# hw-demo03.net
KiCad netlist of a schematic drawn in EAGLE
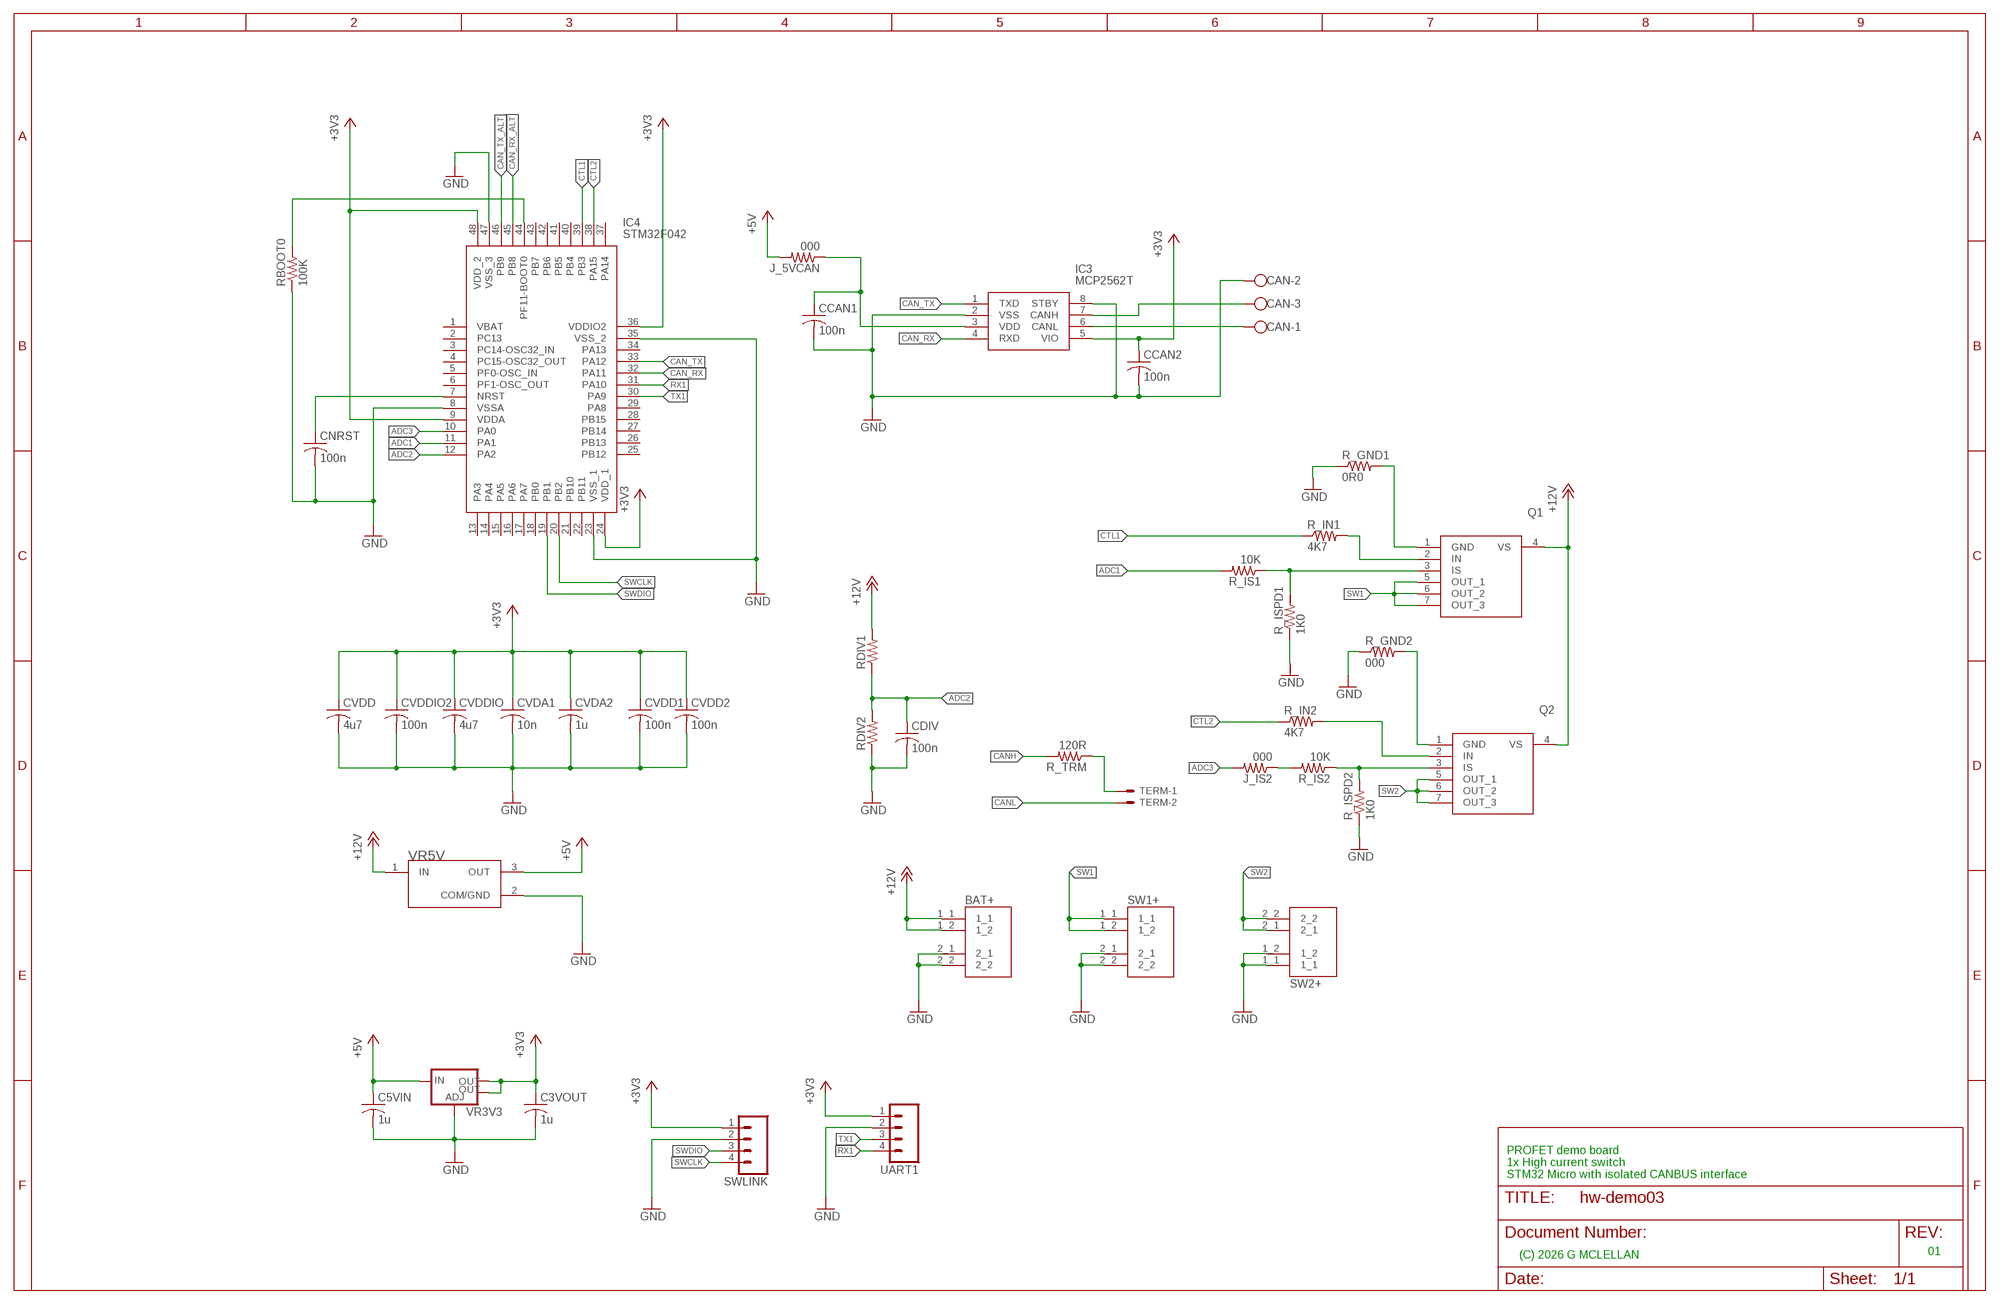
[diagram p0: schematic, sheet 1]

(export (version "E")
  (design (tool "Eeschema 10.0.6"))
  (components
    (comp (ref "BAT+")
      (value "VP0265840000G")
      (footprint "eagle-import:AMPHENOL_VP0265840000G")
      (fields (field (name "MANUFACTURER") "Amphenol Anytek"))
      (libsource (lib "eagle-import") (part "VP0265840000G"))
    )
    (comp (ref "C3VOUT")
      (value "1u")
      (footprint "eagle-import:C0805K")
      (libsource (lib "eagle-import") (part "C-USC0805K"))
    )
    (comp (ref "C5VIN")
      (value "1u")
      (footprint "eagle-import:C1206K")
      (libsource (lib "eagle-import") (part "C-USC1206K"))
    )
    (comp (ref "CAN")
      (value "W237-103")
      (footprint "eagle-import:W237-103")
      (fields (field (name "MPN") "237-103"))
      (libsource (lib "eagle-import") (part "W237-103"))
    )
    (comp (ref "CCAN1")
      (value "100n")
      (footprint "eagle-import:C0603K")
      (libsource (lib "eagle-import") (part "C-USC0603K"))
    )
    (comp (ref "CCAN2")
      (value "100n")
      (footprint "eagle-import:C0603K")
      (libsource (lib "eagle-import") (part "C-USC0603K"))
    )
    (comp (ref "CDIV")
      (value "100n")
      (footprint "eagle-import:C0603K")
      (libsource (lib "eagle-import") (part "C-USC0603K"))
    )
    (comp (ref "CNRST")
      (value "100n")
      (footprint "eagle-import:C0603K")
      (libsource (lib "eagle-import") (part "C-USC0603K"))
    )
    (comp (ref "CVDA1")
      (value "10n")
      (footprint "eagle-import:C0603K")
      (libsource (lib "eagle-import") (part "C-USC0603K"))
    )
    (comp (ref "CVDA2")
      (value "1u")
      (footprint "eagle-import:C0603K")
      (libsource (lib "eagle-import") (part "C-USC0603K"))
    )
    (comp (ref "CVDD")
      (value "4u7")
      (footprint "eagle-import:C0603K")
      (libsource (lib "eagle-import") (part "C-USC0603K"))
    )
    (comp (ref "CVDD1")
      (value "100n")
      (footprint "eagle-import:C0603K")
      (libsource (lib "eagle-import") (part "C-USC0603K"))
    )
    (comp (ref "CVDD2")
      (value "100n")
      (footprint "eagle-import:C0603K")
      (libsource (lib "eagle-import") (part "C-USC0603K"))
    )
    (comp (ref "CVDDIO")
      (value "4u7")
      (footprint "eagle-import:C0603K")
      (libsource (lib "eagle-import") (part "C-USC0603K"))
    )
    (comp (ref "CVDDIO2")
      (value "100n")
      (footprint "eagle-import:C0603K")
      (libsource (lib "eagle-import") (part "C-USC0603K"))
    )
    (comp (ref "IC3")
      (value "MCP2562T")
      (footprint "eagle-import:SOIC127P600X175-8N")
      (fields
        (field (name "MANUFACTURER_PART_NUMBER") "MCP2562T-H/SN")
        (field (name "MOUSER_PART_NUMBER") "579-MCP2562T-H/SN")
      )
      (libsource (lib "eagle-import") (part "MCP2562T-H_SN"))
    )
    (comp (ref "IC4")
      (value "STM32F042")
      (footprint "eagle-import:QFP50P900X900X160-48N")
      (fields
        (field (name "MANUFACTURER_PART_NUMBER") "STM32F042C6T7")
        (field (name "MOUSER_PART_NUMBER") "511-STM32F042C6T7")
      )
      (libsource (lib "eagle-import") (part "STM32F042C6T7"))
    )
    (comp (ref "J_5VCAN")
      (value "000")
      (footprint "eagle-import:0207_15")
      (libsource (lib "eagle-import") (part "R-US_0207/15"))
    )
    (comp (ref "J_IS2")
      (value "000")
      (footprint "eagle-import:0207_15")
      (libsource (lib "eagle-import") (part "R-US_0207/15"))
    )
    (comp (ref "Q1")
      (value "BTS500101TADATMA2")
      (footprint "eagle-import:BTS500101TADATMA2")
      (fields (field (name "MOUSER_PART_NUMBER") "726-BTS500101TADATM2"))
      (libsource (lib "eagle-import") (part "BTS500101TADATMA2"))
    )
    (comp (ref "Q2")
      (value "BTS500101TADATMA2")
      (footprint "eagle-import:BTS500101TADATMA2")
      (fields (field (name "MOUSER_PART_NUMBER") "726-BTS500101TADATM2"))
      (libsource (lib "eagle-import") (part "BTS500101TADATMA2"))
    )
    (comp (ref "RBOOT0")
      (value "100K")
      (footprint "eagle-import:R0603")
      (libsource (lib "eagle-import") (part "R-US_R0603"))
    )
    (comp (ref "RDIV1")
      (value "R-US_R0805")
      (footprint "eagle-import:R0805")
      (libsource (lib "eagle-import") (part "R-US_R0805"))
    )
    (comp (ref "RDIV2")
      (value "R-US_R0805")
      (footprint "eagle-import:R0805")
      (libsource (lib "eagle-import") (part "R-US_R0805"))
    )
    (comp (ref "R_GND1")
      (value "0R0")
      (footprint "eagle-import:R1206W")
      (libsource (lib "eagle-import") (part "R-US_R1206W"))
    )
    (comp (ref "R_GND2")
      (value "000")
      (footprint "eagle-import:R1206W")
      (libsource (lib "eagle-import") (part "R-US_R1206W"))
    )
    (comp (ref "R_IN1")
      (value "4K7")
      (footprint "eagle-import:0207_10")
      (libsource (lib "eagle-import") (part "R-US_0207/10"))
    )
    (comp (ref "R_IN2")
      (value "4K7")
      (footprint "eagle-import:0204_7")
      (libsource (lib "eagle-import") (part "R-US_0204/7"))
    )
    (comp (ref "R_IS1")
      (value "10K")
      (footprint "eagle-import:0204_7")
      (libsource (lib "eagle-import") (part "R-US_0204/7"))
    )
    (comp (ref "R_IS2")
      (value "10K")
      (footprint "eagle-import:0204_7")
      (libsource (lib "eagle-import") (part "R-US_0204/7"))
    )
    (comp (ref "R_ISPD1")
      (value "1K0")
      (footprint "eagle-import:0204_7")
      (libsource (lib "eagle-import") (part "R-US_0204/7"))
    )
    (comp (ref "R_ISPD2")
      (value "1K0")
      (footprint "eagle-import:0204_7")
      (libsource (lib "eagle-import") (part "R-US_0204/7"))
    )
    (comp (ref "R_TRM")
      (value "120R")
      (footprint "eagle-import:0204_7")
      (libsource (lib "eagle-import") (part "R-US_0204/7"))
    )
    (comp (ref "SW1+")
      (value "VP0265840000G")
      (footprint "eagle-import:AMPHENOL_VP0265840000G")
      (fields (field (name "MANUFACTURER") "Amphenol Anytek"))
      (libsource (lib "eagle-import") (part "VP0265840000G"))
    )
    (comp (ref "SW2+")
      (value "VP0265840000G")
      (footprint "eagle-import:AMPHENOL_VP0265840000G")
      (fields (field (name "MANUFACTURER") "Amphenol Anytek"))
      (libsource (lib "eagle-import") (part "VP0265840000G"))
    )
    (comp (ref "SWLINK")
      (value "M04LOCK")
      (footprint "eagle-import:1X04_LOCK")
      (libsource (lib "eagle-import") (part "M04LOCK"))
    )
    (comp (ref "TERM")
      (value "22-23-2021")
      (footprint "eagle-import:22-23-2021")
      (fields (field (name "MF") "MOLEX"))
      (libsource (lib "eagle-import") (part "22-23-2021"))
    )
    (comp (ref "UART1")
      (value "M04LOCK")
      (footprint "eagle-import:1X04_LOCK")
      (libsource (lib "eagle-import") (part "M04LOCK"))
    )
    (comp (ref "VR3V3")
      (value "V_REG_LM1117SOT223")
      (footprint "eagle-import:SOT223")
      (libsource (lib "eagle-import") (part "V_REG_LM1117SOT223"))
    )
    (comp (ref "VR5V")
      (value "OKI-78SR-5/1.5-W36-C")
      (footprint "eagle-import:CONV_OKI-78SR-5_1.5-W36-C")
      (fields (field (name "MANUFACTURER") "Murata"))
      (libsource (lib "eagle-import") (part "OKI-78SR-5/1.5-W36-C"))
    )
  )
  (nets
    (net (code "1") (name "+3V3") (class "Default")
      (node (ref "C3VOUT") (pin "1") (pinfunction "1_1") (pintype "passive"))
      (node (ref "CCAN2") (pin "1") (pinfunction "1_1") (pintype "passive"))
      (node (ref "CVDA1") (pin "1") (pinfunction "1_1") (pintype "passive"))
      (node (ref "CVDA2") (pin "1") (pinfunction "1_1") (pintype "passive"))
      (node (ref "CVDD") (pin "1") (pinfunction "1_1") (pintype "passive"))
      (node (ref "CVDD1") (pin "1") (pinfunction "1_1") (pintype "passive"))
      (node (ref "CVDD2") (pin "1") (pinfunction "1_1") (pintype "passive"))
      (node (ref "CVDDIO") (pin "1") (pinfunction "1_1") (pintype "passive"))
      (node (ref "CVDDIO2") (pin "1") (pinfunction "1_1") (pintype "passive"))
      (node (ref "IC3") (pin "5") (pinfunction "VIO_5") (pintype "bidirectional"))
      (node (ref "IC4") (pin "24") (pinfunction "VDD_1_24") (pintype "bidirectional"))
      (node (ref "IC4") (pin "36") (pinfunction "VDDIO2_36") (pintype "bidirectional"))
      (node (ref "IC4") (pin "48") (pinfunction "VDD_2_48") (pintype "bidirectional"))
      (node (ref "IC4") (pin "9") (pinfunction "VDDA_9") (pintype "bidirectional"))
      (node (ref "SWLINK") (pin "1") (pinfunction "1_1") (pintype "passive"))
      (node (ref "UART1") (pin "1") (pinfunction "1_1") (pintype "passive"))
      (node (ref "VR3V3") (pin "2") (pinfunction "OUT_2") (pintype "output"))
      (node (ref "VR3V3") (pin "4") (pinfunction "OUT_4") (pintype "output"))
    )
    (net (code "2") (name "+5V") (class "Default")
      (node (ref "C5VIN") (pin "1") (pinfunction "1_1") (pintype "passive"))
      (node (ref "J_5VCAN") (pin "2") (pinfunction "2_2") (pintype "passive"))
      (node (ref "VR3V3") (pin "3") (pinfunction "IN_3") (pintype "input"))
      (node (ref "VR5V") (pin "3") (pinfunction "OUT_3") (pintype "output"))
    )
    (net (code "3") (name "+12V") (class "Default")
      (node (ref "BAT+") (pin "1_1") (pinfunction "1_1_1_1") (pintype "passive"))
      (node (ref "BAT+") (pin "1_2") (pinfunction "1_2_1_2") (pintype "passive"))
      (node (ref "Q1") (pin "4") (pinfunction "VS_4") (pintype "bidirectional"))
      (node (ref "Q2") (pin "4") (pinfunction "VS_4") (pintype "bidirectional"))
      (node (ref "RDIV1") (pin "2") (pinfunction "2_2") (pintype "passive"))
      (node (ref "VR5V") (pin "1") (pinfunction "IN_1") (pintype "input"))
    )
    (net (code "4") (name "ADC1") (class "Default")
      (node (ref "IC4") (pin "11") (pinfunction "PA1_11") (pintype "bidirectional"))
      (node (ref "R_IS1") (pin "2") (pinfunction "2_2") (pintype "passive"))
    )
    (net (code "5") (name "ADC2") (class "Default")
      (node (ref "CDIV") (pin "1") (pinfunction "1_1") (pintype "passive"))
      (node (ref "IC4") (pin "12") (pinfunction "PA2_12") (pintype "bidirectional"))
      (node (ref "RDIV1") (pin "1") (pinfunction "1_1") (pintype "passive"))
      (node (ref "RDIV2") (pin "2") (pinfunction "2_2") (pintype "passive"))
    )
    (net (code "6") (name "ADC3") (class "Default")
      (node (ref "IC4") (pin "10") (pinfunction "PA0_10") (pintype "bidirectional"))
      (node (ref "J_IS2") (pin "2") (pinfunction "2_2") (pintype "passive"))
    )
    (net (code "7") (name "CANH") (class "Default")
      (node (ref "CAN") (pin "3") (pinfunction "KL_3") (pintype "passive"))
      (node (ref "IC3") (pin "7") (pinfunction "CANH_7") (pintype "bidirectional"))
      (node (ref "R_TRM") (pin "2") (pinfunction "2_2") (pintype "passive"))
    )
    (net (code "8") (name "CANL") (class "Default")
      (node (ref "CAN") (pin "1") (pinfunction "KL_1") (pintype "passive"))
      (node (ref "IC3") (pin "6") (pinfunction "CANL_6") (pintype "bidirectional"))
      (node (ref "TERM") (pin "2") (pinfunction "S_2") (pintype "passive"))
    )
    (net (code "9") (name "CAN_RX") (class "Default")
      (node (ref "IC3") (pin "4") (pinfunction "RXD_4") (pintype "bidirectional"))
      (node (ref "IC4") (pin "32") (pinfunction "PA11_32") (pintype "bidirectional"))
    )
    (net (code "10") (name "CAN_RX_ALT") (class "Default")
      (node (ref "IC4") (pin "45") (pinfunction "PB8_45") (pintype "bidirectional"))
    )
    (net (code "11") (name "CAN_TX") (class "Default")
      (node (ref "IC3") (pin "1") (pinfunction "TXD_1") (pintype "bidirectional"))
      (node (ref "IC4") (pin "33") (pinfunction "PA12_33") (pintype "bidirectional"))
    )
    (net (code "12") (name "CAN_TX_ALT") (class "Default")
      (node (ref "IC4") (pin "46") (pinfunction "PB9_46") (pintype "bidirectional"))
    )
    (net (code "13") (name "CTL1") (class "Default")
      (node (ref "IC4") (pin "39") (pinfunction "PB3_39") (pintype "bidirectional"))
      (node (ref "R_IN1") (pin "1") (pinfunction "1_1") (pintype "passive"))
    )
    (net (code "14") (name "CTL2") (class "Default")
      (node (ref "IC4") (pin "38") (pinfunction "PA15_38") (pintype "bidirectional"))
      (node (ref "R_IN2") (pin "1") (pinfunction "1_1") (pintype "passive"))
    )
    (net (code "15") (name "GND") (class "Default")
      (node (ref "BAT+") (pin "2_1") (pinfunction "2_1_2_1") (pintype "passive"))
      (node (ref "BAT+") (pin "2_2") (pinfunction "2_2_2_2") (pintype "passive"))
      (node (ref "C3VOUT") (pin "2") (pinfunction "2_2") (pintype "passive"))
      (node (ref "C5VIN") (pin "2") (pinfunction "2_2") (pintype "passive"))
      (node (ref "CAN") (pin "2") (pinfunction "KL_2") (pintype "passive"))
      (node (ref "CCAN1") (pin "2") (pinfunction "2_2") (pintype "passive"))
      (node (ref "CCAN2") (pin "2") (pinfunction "2_2") (pintype "passive"))
      (node (ref "CDIV") (pin "2") (pinfunction "2_2") (pintype "passive"))
      (node (ref "CNRST") (pin "2") (pinfunction "2_2") (pintype "passive"))
      (node (ref "CVDA1") (pin "2") (pinfunction "2_2") (pintype "passive"))
      (node (ref "CVDA2") (pin "2") (pinfunction "2_2") (pintype "passive"))
      (node (ref "CVDD") (pin "2") (pinfunction "2_2") (pintype "passive"))
      (node (ref "CVDD1") (pin "2") (pinfunction "2_2") (pintype "passive"))
      (node (ref "CVDD2") (pin "2") (pinfunction "2_2") (pintype "passive"))
      (node (ref "CVDDIO") (pin "2") (pinfunction "2_2") (pintype "passive"))
      (node (ref "CVDDIO2") (pin "2") (pinfunction "2_2") (pintype "passive"))
      (node (ref "IC3") (pin "2") (pinfunction "VSS_2") (pintype "bidirectional"))
      (node (ref "IC3") (pin "8") (pinfunction "STBY_8") (pintype "bidirectional"))
      (node (ref "IC4") (pin "23") (pinfunction "VSS_1_23") (pintype "bidirectional"))
      (node (ref "IC4") (pin "35") (pinfunction "VSS_2_35") (pintype "bidirectional"))
      (node (ref "IC4") (pin "47") (pinfunction "VSS_3_47") (pintype "bidirectional"))
      (node (ref "IC4") (pin "8") (pinfunction "VSSA_8") (pintype "bidirectional"))
      (node (ref "RBOOT0") (pin "1") (pinfunction "1_1") (pintype "passive"))
      (node (ref "RDIV2") (pin "1") (pinfunction "1_1") (pintype "passive"))
      (node (ref "R_GND1") (pin "1") (pinfunction "1_1") (pintype "passive"))
      (node (ref "R_GND2") (pin "1") (pinfunction "1_1") (pintype "passive"))
      (node (ref "R_ISPD1") (pin "1") (pinfunction "1_1") (pintype "passive"))
      (node (ref "R_ISPD2") (pin "1") (pinfunction "1_1") (pintype "passive"))
      (node (ref "SW1+") (pin "2_1") (pinfunction "2_1_2_1") (pintype "passive"))
      (node (ref "SW1+") (pin "2_2") (pinfunction "2_2_2_2") (pintype "passive"))
      (node (ref "SW2+") (pin "1_1") (pinfunction "1_1_1_1") (pintype "passive"))
      (node (ref "SW2+") (pin "1_2") (pinfunction "1_2_1_2") (pintype "passive"))
      (node (ref "SWLINK") (pin "2") (pinfunction "2_2") (pintype "passive"))
      (node (ref "UART1") (pin "2") (pinfunction "2_2") (pintype "passive"))
      (node (ref "VR3V3") (pin "1") (pinfunction "ADJ_1") (pintype "input"))
      (node (ref "VR5V") (pin "2") (pinfunction "COM/GND_2") (pintype "power_in"))
    )
    (net (code "16") (name "Net-(IC3-VDD)") (class "Default")
      (node (ref "CCAN1") (pin "1") (pinfunction "1_1") (pintype "passive"))
      (node (ref "IC3") (pin "3") (pinfunction "VDD_3") (pintype "bidirectional"))
      (node (ref "J_5VCAN") (pin "1") (pinfunction "1_1") (pintype "passive"))
    )
    (net (code "17") (name "Net-(IC4-NRST)") (class "Default")
      (node (ref "CNRST") (pin "1") (pinfunction "1_1") (pintype "passive"))
      (node (ref "IC4") (pin "7") (pinfunction "NRST_7") (pintype "bidirectional"))
    )
    (net (code "18") (name "Net-(IC4-PF11-BOOT0)") (class "Default")
      (node (ref "IC4") (pin "44") (pinfunction "PF11-BOOT0_44") (pintype "bidirectional"))
      (node (ref "RBOOT0") (pin "2") (pinfunction "2_2") (pintype "passive"))
    )
    (net (code "19") (name "Net-(J_IS2-Pad1)") (class "Default")
      (node (ref "J_IS2") (pin "1") (pinfunction "1_1") (pintype "passive"))
      (node (ref "R_IS2") (pin "2") (pinfunction "2_2") (pintype "passive"))
    )
    (net (code "20") (name "Net-(Q1-GND)") (class "Default")
      (node (ref "Q1") (pin "1") (pinfunction "GND_1") (pintype "bidirectional"))
      (node (ref "R_GND1") (pin "2") (pinfunction "2_2") (pintype "passive"))
    )
    (net (code "21") (name "Net-(Q1-IN)") (class "Default")
      (node (ref "Q1") (pin "2") (pinfunction "IN_2") (pintype "bidirectional"))
      (node (ref "R_IN1") (pin "2") (pinfunction "2_2") (pintype "passive"))
    )
    (net (code "22") (name "Net-(Q1-IS)") (class "Default")
      (node (ref "Q1") (pin "3") (pinfunction "IS_3") (pintype "bidirectional"))
      (node (ref "R_IS1") (pin "1") (pinfunction "1_1") (pintype "passive"))
      (node (ref "R_ISPD1") (pin "2") (pinfunction "2_2") (pintype "passive"))
    )
    (net (code "23") (name "Net-(Q2-GND)") (class "Default")
      (node (ref "Q2") (pin "1") (pinfunction "GND_1") (pintype "bidirectional"))
      (node (ref "R_GND2") (pin "2") (pinfunction "2_2") (pintype "passive"))
    )
    (net (code "24") (name "Net-(Q2-IN)") (class "Default")
      (node (ref "Q2") (pin "2") (pinfunction "IN_2") (pintype "bidirectional"))
      (node (ref "R_IN2") (pin "2") (pinfunction "2_2") (pintype "passive"))
    )
    (net (code "25") (name "Net-(Q2-IS)") (class "Default")
      (node (ref "Q2") (pin "3") (pinfunction "IS_3") (pintype "bidirectional"))
      (node (ref "R_IS2") (pin "1") (pinfunction "1_1") (pintype "passive"))
      (node (ref "R_ISPD2") (pin "2") (pinfunction "2_2") (pintype "passive"))
    )
    (net (code "26") (name "Net-(TERMA-S)") (class "Default")
      (node (ref "R_TRM") (pin "1") (pinfunction "1_1") (pintype "passive"))
      (node (ref "TERM") (pin "1") (pinfunction "S_1") (pintype "passive"))
    )
    (net (code "27") (name "RX1") (class "Default")
      (node (ref "IC4") (pin "31") (pinfunction "PA10_31") (pintype "bidirectional"))
      (node (ref "UART1") (pin "4") (pinfunction "4_4") (pintype "passive"))
    )
    (net (code "28") (name "SW1") (class "Default")
      (node (ref "Q1") (pin "5") (pinfunction "OUT_1_5") (pintype "bidirectional"))
      (node (ref "Q1") (pin "6") (pinfunction "OUT_2_6") (pintype "bidirectional"))
      (node (ref "Q1") (pin "7") (pinfunction "OUT_3_7") (pintype "bidirectional"))
      (node (ref "SW1+") (pin "1_1") (pinfunction "1_1_1_1") (pintype "passive"))
      (node (ref "SW1+") (pin "1_2") (pinfunction "1_2_1_2") (pintype "passive"))
    )
    (net (code "29") (name "SW2") (class "Default")
      (node (ref "Q2") (pin "5") (pinfunction "OUT_1_5") (pintype "bidirectional"))
      (node (ref "Q2") (pin "6") (pinfunction "OUT_2_6") (pintype "bidirectional"))
      (node (ref "Q2") (pin "7") (pinfunction "OUT_3_7") (pintype "bidirectional"))
      (node (ref "SW2+") (pin "2_1") (pinfunction "2_1_2_1") (pintype "passive"))
      (node (ref "SW2+") (pin "2_2") (pinfunction "2_2_2_2") (pintype "passive"))
    )
    (net (code "30") (name "SWCLK") (class "Default")
      (node (ref "IC4") (pin "20") (pinfunction "PB2_20") (pintype "bidirectional"))
      (node (ref "SWLINK") (pin "4") (pinfunction "4_4") (pintype "passive"))
    )
    (net (code "31") (name "SWDIO") (class "Default")
      (node (ref "IC4") (pin "19") (pinfunction "PB1_19") (pintype "bidirectional"))
      (node (ref "SWLINK") (pin "3") (pinfunction "3_3") (pintype "passive"))
    )
    (net (code "32") (name "TX1") (class "Default")
      (node (ref "IC4") (pin "30") (pinfunction "PA9_30") (pintype "bidirectional"))
      (node (ref "UART1") (pin "3") (pinfunction "3_3") (pintype "passive"))
    )
    (net (code "33") (name "unconnected-(IC4-PA3-Pad13)") (class "Default")
      (node (ref "IC4") (pin "13") (pinfunction "PA3_13") (pintype "bidirectional"))
    )
    (net (code "34") (name "unconnected-(IC4-PA4-Pad14)") (class "Default")
      (node (ref "IC4") (pin "14") (pinfunction "PA4_14") (pintype "bidirectional"))
    )
    (net (code "35") (name "unconnected-(IC4-PA5-Pad15)") (class "Default")
      (node (ref "IC4") (pin "15") (pinfunction "PA5_15") (pintype "bidirectional"))
    )
    (net (code "36") (name "unconnected-(IC4-PA6-Pad16)") (class "Default")
      (node (ref "IC4") (pin "16") (pinfunction "PA6_16") (pintype "bidirectional"))
    )
    (net (code "37") (name "unconnected-(IC4-PA7-Pad17)") (class "Default")
      (node (ref "IC4") (pin "17") (pinfunction "PA7_17") (pintype "bidirectional"))
    )
    (net (code "38") (name "unconnected-(IC4-PA8-Pad29)") (class "Default")
      (node (ref "IC4") (pin "29") (pinfunction "PA8_29") (pintype "bidirectional"))
    )
    (net (code "39") (name "unconnected-(IC4-PA13-Pad34)") (class "Default")
      (node (ref "IC4") (pin "34") (pinfunction "PA13_34") (pintype "bidirectional"))
    )
    (net (code "40") (name "unconnected-(IC4-PA14-Pad37)") (class "Default")
      (node (ref "IC4") (pin "37") (pinfunction "PA14_37") (pintype "bidirectional"))
    )
    (net (code "41") (name "unconnected-(IC4-PB0-Pad18)") (class "Default")
      (node (ref "IC4") (pin "18") (pinfunction "PB0_18") (pintype "bidirectional"))
    )
    (net (code "42") (name "unconnected-(IC4-PB4-Pad40)") (class "Default")
      (node (ref "IC4") (pin "40") (pinfunction "PB4_40") (pintype "bidirectional"))
    )
    (net (code "43") (name "unconnected-(IC4-PB5-Pad41)") (class "Default")
      (node (ref "IC4") (pin "41") (pinfunction "PB5_41") (pintype "bidirectional"))
    )
    (net (code "44") (name "unconnected-(IC4-PB6-Pad42)") (class "Default")
      (node (ref "IC4") (pin "42") (pinfunction "PB6_42") (pintype "bidirectional"))
    )
    (net (code "45") (name "unconnected-(IC4-PB7-Pad43)") (class "Default")
      (node (ref "IC4") (pin "43") (pinfunction "PB7_43") (pintype "bidirectional"))
    )
    (net (code "46") (name "unconnected-(IC4-PB10-Pad21)") (class "Default")
      (node (ref "IC4") (pin "21") (pinfunction "PB10_21") (pintype "bidirectional"))
    )
    (net (code "47") (name "unconnected-(IC4-PB11-Pad22)") (class "Default")
      (node (ref "IC4") (pin "22") (pinfunction "PB11_22") (pintype "bidirectional"))
    )
    (net (code "48") (name "unconnected-(IC4-PB12-Pad25)") (class "Default")
      (node (ref "IC4") (pin "25") (pinfunction "PB12_25") (pintype "bidirectional"))
    )
    (net (code "49") (name "unconnected-(IC4-PB13-Pad26)") (class "Default")
      (node (ref "IC4") (pin "26") (pinfunction "PB13_26") (pintype "bidirectional"))
    )
    (net (code "50") (name "unconnected-(IC4-PB14-Pad27)") (class "Default")
      (node (ref "IC4") (pin "27") (pinfunction "PB14_27") (pintype "bidirectional"))
    )
    (net (code "51") (name "unconnected-(IC4-PB15-Pad28)") (class "Default")
      (node (ref "IC4") (pin "28") (pinfunction "PB15_28") (pintype "bidirectional"))
    )
    (net (code "52") (name "unconnected-(IC4-PC13-Pad2)") (class "Default")
      (node (ref "IC4") (pin "2") (pinfunction "PC13_2") (pintype "bidirectional"))
    )
    (net (code "53") (name "unconnected-(IC4-PC14-OSC32_IN-Pad3)") (class "Default")
      (node (ref "IC4") (pin "3") (pinfunction "PC14-OSC32_IN_3") (pintype "bidirectional"))
    )
    (net (code "54") (name "unconnected-(IC4-PC15-OSC32_OUT-Pad4)") (class "Default")
      (node (ref "IC4") (pin "4") (pinfunction "PC15-OSC32_OUT_4") (pintype "bidirectional"))
    )
    (net (code "55") (name "unconnected-(IC4-PF0-OSC_IN-Pad5)") (class "Default")
      (node (ref "IC4") (pin "5") (pinfunction "PF0-OSC_IN_5") (pintype "bidirectional"))
    )
    (net (code "56") (name "unconnected-(IC4-PF1-OSC_OUT-Pad6)") (class "Default")
      (node (ref "IC4") (pin "6") (pinfunction "PF1-OSC_OUT_6") (pintype "bidirectional"))
    )
    (net (code "57") (name "unconnected-(IC4-VBAT-Pad1)") (class "Default")
      (node (ref "IC4") (pin "1") (pinfunction "VBAT_1") (pintype "bidirectional"))
    )
  )
)
